# ADS1248_Eval_Board.net
KiCad netlist of a schematic drawn in EasyEDA
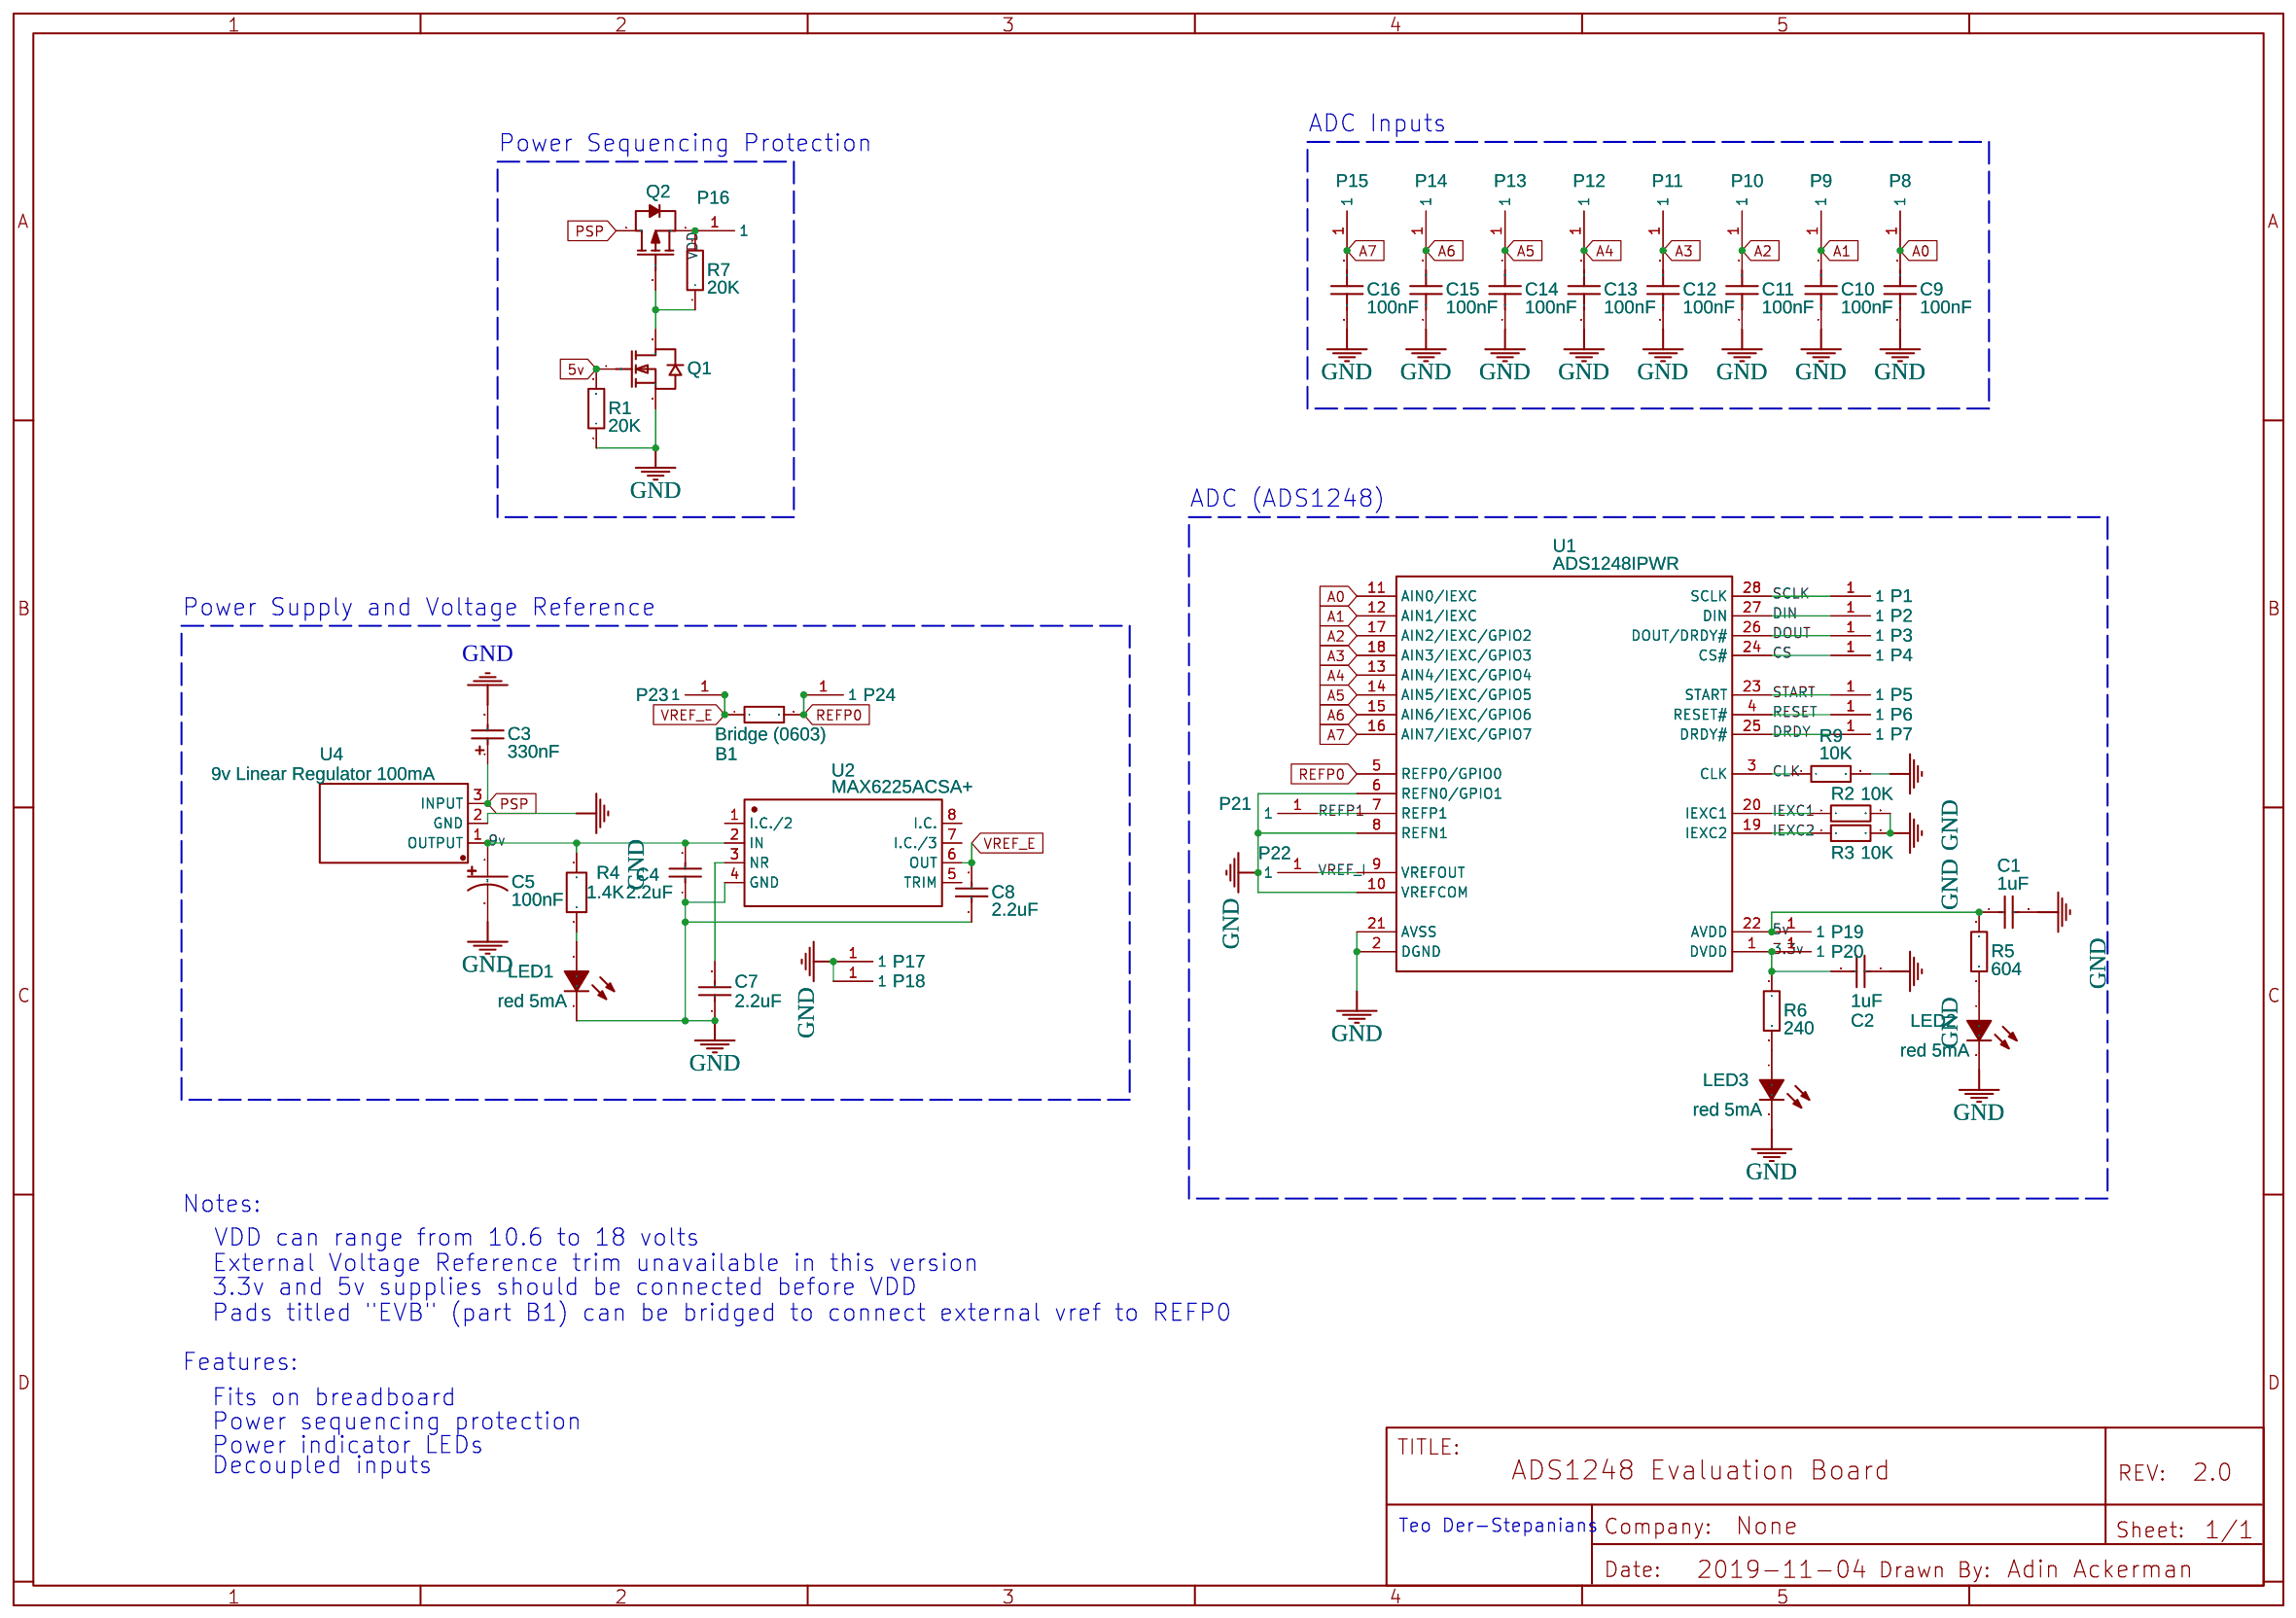
[diagram p0: schematic sheet]

(export (version "E")
  (design (tool "Eeschema 10.0.6"))
  (components
    (comp (ref "B1") (value "Bridge (0603)") (libsource (lib "") (part "Unknown_380_355")))
    (comp (ref "C1")
      (value "1uF")
      (fields
        (field (name "BOM_Manufacturer Part") "CL21B105KOFNNNE")
        (field (name "BOM_Supplier Part") "C24123")
      )
      (libsource (lib "") (part "CL21B105KOFNNNE"))
    )
    (comp (ref "C2")
      (value "1uF")
      (fields
        (field (name "BOM_Manufacturer Part") "CL21B105KOFNNNE")
        (field (name "BOM_Supplier Part") "C24123")
      )
      (libsource (lib "") (part "CL21B105KOFNNNE"))
    )
    (comp (ref "C3")
      (value "330nF")
      (fields
        (field (name "BOM_Manufacturer Part") "F921V334MAA")
        (field (name "BOM_Supplier Part") "C382101")
      )
      (libsource (lib "") (part "F921V334MAA"))
    )
    (comp (ref "C4")
      (value "2.2uF")
      (fields
        (field (name "BOM_Manufacturer Part") "CL21A225KAFNNNE")
        (field (name "BOM_Supplier Part") "C87994")
      )
      (libsource (lib "") (part "CL21A225KAFNNNE"))
    )
    (comp (ref "C5")
      (value "100nF")
      (fields
        (field (name "BOM_Manufacturer Part") "TMCP1D104MTRF")
        (field (name "BOM_Supplier Part") "C154088")
      )
      (libsource (lib "") (part "TMCP1D104MTRF"))
    )
    (comp (ref "C7")
      (value "2.2uF")
      (fields
        (field (name "BOM_Manufacturer Part") "CL21A225KAFNNNE")
        (field (name "BOM_Supplier Part") "C87994")
      )
      (libsource (lib "") (part "CL21A225KAFNNNE"))
    )
    (comp (ref "C8")
      (value "2.2uF")
      (fields
        (field (name "BOM_Manufacturer Part") "CL21A225KAFNNNE")
        (field (name "BOM_Supplier Part") "C87994")
      )
      (libsource (lib "") (part "CL21A225KAFNNNE"))
    )
    (comp (ref "C9")
      (value "100nF")
      (fields
        (field (name "BOM_Manufacturer Part") "CL10B104KB8NNNC")
        (field (name "BOM_Supplier Part") "C1591")
      )
      (libsource (lib "") (part "CL10B104KB8NNNC"))
    )
    (comp (ref "C10")
      (value "100nF")
      (fields
        (field (name "BOM_Manufacturer Part") "CL10B104KB8NNNC")
        (field (name "BOM_Supplier Part") "C1591")
      )
      (libsource (lib "") (part "CL10B104KB8NNNC"))
    )
    (comp (ref "C11")
      (value "100nF")
      (fields
        (field (name "BOM_Manufacturer Part") "CL10B104KB8NNNC")
        (field (name "BOM_Supplier Part") "C1591")
      )
      (libsource (lib "") (part "CL10B104KB8NNNC"))
    )
    (comp (ref "C12")
      (value "100nF")
      (fields
        (field (name "BOM_Manufacturer Part") "CL10B104KB8NNNC")
        (field (name "BOM_Supplier Part") "C1591")
      )
      (libsource (lib "") (part "CL10B104KB8NNNC"))
    )
    (comp (ref "C13")
      (value "100nF")
      (fields
        (field (name "BOM_Manufacturer Part") "CL10B104KB8NNNC")
        (field (name "BOM_Supplier Part") "C1591")
      )
      (libsource (lib "") (part "CL10B104KB8NNNC"))
    )
    (comp (ref "C14")
      (value "100nF")
      (fields
        (field (name "BOM_Manufacturer Part") "CL10B104KB8NNNC")
        (field (name "BOM_Supplier Part") "C1591")
      )
      (libsource (lib "") (part "CL10B104KB8NNNC"))
    )
    (comp (ref "C15")
      (value "100nF")
      (fields
        (field (name "BOM_Manufacturer Part") "CL10B104KB8NNNC")
        (field (name "BOM_Supplier Part") "C1591")
      )
      (libsource (lib "") (part "CL10B104KB8NNNC"))
    )
    (comp (ref "C16")
      (value "100nF")
      (fields
        (field (name "BOM_Manufacturer Part") "CL10B104KB8NNNC")
        (field (name "BOM_Supplier Part") "C1591")
      )
      (libsource (lib "") (part "CL10B104KB8NNNC"))
    )
    (comp (ref "LED1")
      (value "red 5mA")
      (fields
        (field (name "BOM_Manufacturer Part") "19-217/R6C-AL1M2VY/3T(GDB)")
        (field (name "BOM_Supplier Part") "C131266")
      )
      (libsource (lib "") (part "Unknown_295_490"))
    )
    (comp (ref "LED2")
      (value "red 5mA")
      (fields
        (field (name "BOM_Manufacturer Part") "19-217/R6C-AL1M2VY/3T(GDB)")
        (field (name "BOM_Supplier Part") "C131266")
      )
      (libsource (lib "") (part "Unknown_1005_515"))
    )
    (comp (ref "LED3")
      (value "red 5mA")
      (fields
        (field (name "BOM_Manufacturer Part") "19-217/R6C-AL1M2VY/3T(GDB)")
        (field (name "BOM_Supplier Part") "C131266")
      )
      (libsource (lib "") (part "Unknown_900_545"))
    )
    (comp (ref "P1") (value "Standard 100 mil pad") (libsource (lib "") (part "Unknown_920_295")))
    (comp (ref "P2") (value "Standard 100 mil pad") (libsource (lib "") (part "Unknown_920_305")))
    (comp (ref "P3") (value "Standard 100 mil pad") (libsource (lib "") (part "Unknown_920_315")))
    (comp (ref "P4") (value "Standard 100 mil pad") (libsource (lib "") (part "Unknown_920_325")))
    (comp (ref "P5") (value "Standard 100 mil pad") (libsource (lib "") (part "Unknown_920_345")))
    (comp (ref "P6") (value "Standard 100 mil pad") (libsource (lib "") (part "Unknown_920_355")))
    (comp (ref "P7") (value "Standard 100 mil pad") (libsource (lib "") (part "Unknown_920_365")))
    (comp (ref "P8") (value "Standard 100 mil pad") (libsource (lib "") (part "Unknown_955_120")))
    (comp (ref "P9") (value "Standard 100 mil pad") (libsource (lib "") (part "Unknown_915_120")))
    (comp (ref "P10") (value "Standard 100 mil pad") (libsource (lib "") (part "Unknown_875_120")))
    (comp (ref "P11") (value "Standard 100 mil pad") (libsource (lib "") (part "Unknown_835_120")))
    (comp (ref "P12") (value "Standard 100 mil pad") (libsource (lib "") (part "Unknown_795_120")))
    (comp (ref "P13") (value "Standard 100 mil pad") (libsource (lib "") (part "Unknown_755_120")))
    (comp (ref "P14") (value "Standard 100 mil pad") (libsource (lib "") (part "Unknown_715_120")))
    (comp (ref "P15") (value "Standard 100 mil pad") (libsource (lib "") (part "Unknown_675_120")))
    (comp (ref "P16") (value "Standard 100 mil pad") (libsource (lib "") (part "Unknown_345_110")))
    (comp (ref "P17") (value "Standard 100 mil pad") (libsource (lib "") (part "Unknown_415_480")))
    (comp (ref "P18") (value "Standard 100 mil pad") (libsource (lib "") (part "Unknown_415_490")))
    (comp (ref "P19") (value "Standard 100 mil pad") (libsource (lib "") (part "Unknown_890_465")))
    (comp (ref "P20") (value "Standard 100 mil pad") (libsource (lib "") (part "Unknown_890_475")))
    (comp (ref "P21") (value "Standard 100 mil pad") (libsource (lib "") (part "Unknown_660_405")))
    (comp (ref "P22") (value "Standard 100 mil pad") (libsource (lib "") (part "Unknown_660_435")))
    (comp (ref "P23") (value "Standard 100 mil pad") (libsource (lib "") (part "Unknown_360_345")))
    (comp (ref "P24") (value "Standard 100 mil pad") (libsource (lib "") (part "Unknown_400_345")))
    (comp (ref "Q1")
      (value "AO3402_C14385")
      (fields (field (name "BOM_Manufacturer Part") "AO3402") (field (name "BOM_Supplier Part") "C14385"))
      (libsource (lib "") (part "Unknown_315_180"))
    )
    (comp (ref "Q2")
      (value "AO3407A")
      (fields (field (name "BOM_Supplier Part") "C15155"))
      (libsource (lib "") (part "Unknown_325_120"))
    )
    (comp (ref "R1")
      (value "20K")
      (fields
        (field (name "BOM_Manufacturer Part") "RC0603FR-0720KL")
        (field (name "BOM_Supplier Part") "C105575")
      )
      (libsource (lib "") (part "RC0603FR-0720KL"))
    )
    (comp (ref "R2")
      (value "10K")
      (fields
        (field (name "BOM_Manufacturer Part") "RC0603FR-0710KL")
        (field (name "BOM_Supplier Part") "C98220")
      )
      (libsource (lib "") (part "RC0603FR-0710KL"))
    )
    (comp (ref "R3")
      (value "10K")
      (fields
        (field (name "BOM_Manufacturer Part") "RC0603FR-0710KL")
        (field (name "BOM_Supplier Part") "C98220")
      )
      (libsource (lib "") (part "RC0603FR-0710KL"))
    )
    (comp (ref "R4")
      (value "1.4K")
      (fields
        (field (name "BOM_Manufacturer Part") "ERJ3EKF1401V")
        (field (name "BOM_Supplier Part") "C402982")
      )
      (libsource (lib "") (part "ERJ3EKF1401V"))
    )
    (comp (ref "R5")
      (value "604")
      (fields
        (field (name "BOM_Manufacturer Part") "AC0603FR-07604RL")
        (field (name "BOM_Supplier Part") "C227993")
      )
      (libsource (lib "") (part "AC0603FR-07604RL"))
    )
    (comp (ref "R6")
      (value "240")
      (fields
        (field (name "BOM_Manufacturer Part") "0805W8F2400T5E")
        (field (name "BOM_Supplier Part") "C17572")
      )
      (libsource (lib "") (part "0805W8F2400T5E"))
    )
    (comp (ref "R7")
      (value "20K")
      (fields
        (field (name "BOM_Manufacturer Part") "RC0603FR-0720KL")
        (field (name "BOM_Supplier Part") "C105575")
      )
      (libsource (lib "") (part "RC0603FR-0720KL"))
    )
    (comp (ref "R9")
      (value "10K")
      (fields
        (field (name "BOM_Manufacturer Part") "RC0603FR-0710KL")
        (field (name "BOM_Supplier Part") "C98220")
      )
      (libsource (lib "") (part "RC0603FR-0710KL"))
    )
    (comp (ref "U1")
      (value "ADS1248IPWR")
      (fields (field (name "BOM_Supplier Part") "C30576"))
      (libsource (lib "") (part "Unknown_790_385"))
    )
    (comp (ref "U2") (value "MAX6225ACSA+") (libsource (lib "") (part "Unknown_420_425")))
    (comp (ref "U4")
      (value "9v Linear Regulator 100mA")
      (fields
        (field (name "BOM_Manufacturer Part") "AZ78L09RTR-E1")
        (field (name "BOM_Supplier Part") "C108741")
      )
      (libsource (lib "") (part "Unknown_190_410"))
    )
  )
  (nets
    (net (code "1") (name "/3.3v") (class "Default")
      (node (ref "C2") (pin "1") (pinfunction "1_1") (pintype "input"))
      (node (ref "P20") (pin "1") (pinfunction "1_1") (pintype "unspecified"))
      (node (ref "R6") (pin "1") (pinfunction "1_1") (pintype "input"))
      (node (ref "U1") (pin "1") (pinfunction "DVDD_1") (pintype "unspecified"))
    )
    (net (code "2") (name "/9v") (class "Default")
      (node (ref "C4") (pin "2") (pinfunction "2_2") (pintype "input"))
      (node (ref "C5") (pin "1") (pinfunction "1_1") (pintype "unspecified"))
      (node (ref "R4") (pin "2") (pinfunction "2_2") (pintype "unspecified"))
      (node (ref "U2") (pin "2") (pinfunction "IN_2") (pintype "unspecified"))
      (node (ref "U4") (pin "1") (pinfunction "OUTPUT_1") (pintype "unspecified"))
    )
    (net (code "3") (name "/CLK") (class "Default")
      (node (ref "R9") (pin "1") (pinfunction "1_1") (pintype "input"))
      (node (ref "U1") (pin "3") (pinfunction "CLK_3") (pintype "unspecified"))
    )
    (net (code "4") (name "/CS") (class "Default")
      (node (ref "P4") (pin "1") (pinfunction "1_1") (pintype "unspecified"))
      (node (ref "U1") (pin "24") (pinfunction "CS#_24") (pintype "unspecified"))
    )
    (net (code "5") (name "/DIN") (class "Default")
      (node (ref "P2") (pin "1") (pinfunction "1_1") (pintype "unspecified"))
      (node (ref "U1") (pin "27") (pinfunction "DIN_27") (pintype "unspecified"))
    )
    (net (code "6") (name "/DOUT") (class "Default")
      (node (ref "P3") (pin "1") (pinfunction "1_1") (pintype "unspecified"))
      (node (ref "U1") (pin "26") (pinfunction "DOUT/DRDY#_26") (pintype "unspecified"))
    )
    (net (code "7") (name "/DRDY") (class "Default")
      (node (ref "P7") (pin "1") (pinfunction "1_1") (pintype "unspecified"))
      (node (ref "U1") (pin "25") (pinfunction "DRDY#_25") (pintype "unspecified"))
    )
    (net (code "8") (name "/IEXC1") (class "Default")
      (node (ref "R2") (pin "1") (pinfunction "1_1") (pintype "input"))
      (node (ref "U1") (pin "20") (pinfunction "IEXC1_20") (pintype "unspecified"))
    )
    (net (code "9") (name "/IEXC2") (class "Default")
      (node (ref "R3") (pin "1") (pinfunction "1_1") (pintype "input"))
      (node (ref "U1") (pin "19") (pinfunction "IEXC2_19") (pintype "unspecified"))
    )
    (net (code "10") (name "/REFP1") (class "Default")
      (node (ref "P21") (pin "1") (pinfunction "1_1") (pintype "unspecified"))
      (node (ref "U1") (pin "7") (pinfunction "REFP1_7") (pintype "unspecified"))
    )
    (net (code "11") (name "/RESET") (class "Default")
      (node (ref "P6") (pin "1") (pinfunction "1_1") (pintype "unspecified"))
      (node (ref "U1") (pin "4") (pinfunction "RESET#_4") (pintype "unspecified"))
    )
    (net (code "12") (name "/SCLK") (class "Default")
      (node (ref "P1") (pin "1") (pinfunction "1_1") (pintype "unspecified"))
      (node (ref "U1") (pin "28") (pinfunction "SCLK_28") (pintype "unspecified"))
    )
    (net (code "13") (name "/START") (class "Default")
      (node (ref "P5") (pin "1") (pinfunction "1_1") (pintype "unspecified"))
      (node (ref "U1") (pin "23") (pinfunction "START_23") (pintype "unspecified"))
    )
    (net (code "14") (name "/VDD") (class "Default")
      (node (ref "P16") (pin "1") (pinfunction "1_1") (pintype "unspecified"))
      (node (ref "Q2") (pin "2") (pinfunction "S_2") (pintype "unspecified"))
      (node (ref "R7") (pin "2") (pinfunction "2_2") (pintype "input"))
    )
    (net (code "15") (name "/VREF_I") (class "Default")
      (node (ref "P22") (pin "1") (pinfunction "1_1") (pintype "unspecified"))
      (node (ref "U1") (pin "9") (pinfunction "VREFOUT_9") (pintype "unspecified"))
    )
    (net (code "16") (name "5v") (class "Default")
      (node (ref "C1") (pin "1") (pinfunction "1_1") (pintype "input"))
      (node (ref "P19") (pin "1") (pinfunction "1_1") (pintype "unspecified"))
      (node (ref "Q1") (pin "1") (pinfunction "G_1") (pintype "unspecified"))
      (node (ref "R1") (pin "2") (pinfunction "2_2") (pintype "input"))
      (node (ref "R5") (pin "2") (pinfunction "2_2") (pintype "unspecified"))
      (node (ref "U1") (pin "22") (pinfunction "AVDD_22") (pintype "unspecified"))
    )
    (net (code "17") (name "A0") (class "Default")
      (node (ref "C9") (pin "2") (pinfunction "2_2") (pintype "unspecified"))
      (node (ref "P8") (pin "1") (pinfunction "1_1") (pintype "unspecified"))
      (node (ref "U1") (pin "11") (pinfunction "AIN0/IEXC_11") (pintype "unspecified"))
    )
    (net (code "18") (name "A1") (class "Default")
      (node (ref "C10") (pin "2") (pinfunction "2_2") (pintype "unspecified"))
      (node (ref "P9") (pin "1") (pinfunction "1_1") (pintype "unspecified"))
      (node (ref "U1") (pin "12") (pinfunction "AIN1/IEXC_12") (pintype "unspecified"))
    )
    (net (code "19") (name "A2") (class "Default")
      (node (ref "C11") (pin "2") (pinfunction "2_2") (pintype "unspecified"))
      (node (ref "P10") (pin "1") (pinfunction "1_1") (pintype "unspecified"))
      (node (ref "U1") (pin "17") (pinfunction "AIN2/IEXC/GPIO2_17") (pintype "unspecified"))
    )
    (net (code "20") (name "A3") (class "Default")
      (node (ref "C12") (pin "2") (pinfunction "2_2") (pintype "unspecified"))
      (node (ref "P11") (pin "1") (pinfunction "1_1") (pintype "unspecified"))
      (node (ref "U1") (pin "18") (pinfunction "AIN3/IEXC/GPIO3_18") (pintype "unspecified"))
    )
    (net (code "21") (name "A4") (class "Default")
      (node (ref "C13") (pin "2") (pinfunction "2_2") (pintype "unspecified"))
      (node (ref "P12") (pin "1") (pinfunction "1_1") (pintype "unspecified"))
      (node (ref "U1") (pin "13") (pinfunction "AIN4/IEXC/GPIO4_13") (pintype "unspecified"))
    )
    (net (code "22") (name "A5") (class "Default")
      (node (ref "C14") (pin "2") (pinfunction "2_2") (pintype "unspecified"))
      (node (ref "P13") (pin "1") (pinfunction "1_1") (pintype "unspecified"))
      (node (ref "U1") (pin "14") (pinfunction "AIN5/IEXC/GPIO5_14") (pintype "unspecified"))
    )
    (net (code "23") (name "A6") (class "Default")
      (node (ref "C15") (pin "2") (pinfunction "2_2") (pintype "unspecified"))
      (node (ref "P14") (pin "1") (pinfunction "1_1") (pintype "unspecified"))
      (node (ref "U1") (pin "15") (pinfunction "AIN6/IEXC/GPIO6_15") (pintype "unspecified"))
    )
    (net (code "24") (name "A7") (class "Default")
      (node (ref "C16") (pin "2") (pinfunction "2_2") (pintype "unspecified"))
      (node (ref "P15") (pin "1") (pinfunction "1_1") (pintype "unspecified"))
      (node (ref "U1") (pin "16") (pinfunction "AIN7/IEXC/GPIO7_16") (pintype "unspecified"))
    )
    (net (code "25") (name "GND") (class "Default")
      (node (ref "C1") (pin "2") (pinfunction "2_2") (pintype "input"))
      (node (ref "C10") (pin "1") (pinfunction "1_1") (pintype "unspecified"))
      (node (ref "C11") (pin "1") (pinfunction "1_1") (pintype "unspecified"))
      (node (ref "C12") (pin "1") (pinfunction "1_1") (pintype "unspecified"))
      (node (ref "C13") (pin "1") (pinfunction "1_1") (pintype "unspecified"))
      (node (ref "C14") (pin "1") (pinfunction "1_1") (pintype "unspecified"))
      (node (ref "C15") (pin "1") (pinfunction "1_1") (pintype "unspecified"))
      (node (ref "C16") (pin "1") (pinfunction "1_1") (pintype "unspecified"))
      (node (ref "C2") (pin "2") (pinfunction "2_2") (pintype "input"))
      (node (ref "C3") (pin "2") (pinfunction "2_2") (pintype "input"))
      (node (ref "C4") (pin "1") (pinfunction "1_1") (pintype "input"))
      (node (ref "C5") (pin "2") (pinfunction "2_2") (pintype "unspecified"))
      (node (ref "C7") (pin "1") (pinfunction "1_1") (pintype "input"))
      (node (ref "C8") (pin "1") (pinfunction "1_1") (pintype "input"))
      (node (ref "C9") (pin "1") (pinfunction "1_1") (pintype "unspecified"))
      (node (ref "LED1") (pin "2") (pinfunction "C_2") (pintype "input"))
      (node (ref "LED2") (pin "2") (pinfunction "C_2") (pintype "input"))
      (node (ref "LED3") (pin "2") (pinfunction "C_2") (pintype "input"))
      (node (ref "P17") (pin "1") (pinfunction "1_1") (pintype "unspecified"))
      (node (ref "P18") (pin "1") (pinfunction "1_1") (pintype "unspecified"))
      (node (ref "Q1") (pin "2") (pinfunction "S_2") (pintype "unspecified"))
      (node (ref "R1") (pin "1") (pinfunction "1_1") (pintype "input"))
      (node (ref "R2") (pin "2") (pinfunction "2_2") (pintype "input"))
      (node (ref "R3") (pin "2") (pinfunction "2_2") (pintype "input"))
      (node (ref "R9") (pin "2") (pinfunction "2_2") (pintype "input"))
      (node (ref "U1") (pin "10") (pinfunction "VREFCOM_10") (pintype "unspecified"))
      (node (ref "U1") (pin "2") (pinfunction "DGND_2") (pintype "unspecified"))
      (node (ref "U1") (pin "21") (pinfunction "AVSS_21") (pintype "unspecified"))
      (node (ref "U1") (pin "6") (pinfunction "REFN0/GPIO1_6") (pintype "unspecified"))
      (node (ref "U1") (pin "8") (pinfunction "REFN1_8") (pintype "unspecified"))
      (node (ref "U2") (pin "4") (pinfunction "GND_4") (pintype "unspecified"))
      (node (ref "U4") (pin "2") (pinfunction "GND_2") (pintype "unspecified"))
    )
    (net (code "26") (name "Net-(LED1-A)") (class "Default")
      (node (ref "LED1") (pin "1") (pinfunction "A_1") (pintype "input"))
      (node (ref "R4") (pin "1") (pinfunction "1_1") (pintype "unspecified"))
    )
    (net (code "27") (name "Net-(LED2-A)") (class "Default")
      (node (ref "LED2") (pin "1") (pinfunction "A_1") (pintype "input"))
      (node (ref "R5") (pin "1") (pinfunction "1_1") (pintype "unspecified"))
    )
    (net (code "28") (name "Net-(LED3-A)") (class "Default")
      (node (ref "LED3") (pin "1") (pinfunction "A_1") (pintype "input"))
      (node (ref "R6") (pin "2") (pinfunction "2_2") (pintype "input"))
    )
    (net (code "29") (name "Net-(Q1-D)") (class "Default")
      (node (ref "Q1") (pin "3") (pinfunction "D_3") (pintype "unspecified"))
      (node (ref "Q2") (pin "1") (pinfunction "G_1") (pintype "unspecified"))
      (node (ref "R7") (pin "1") (pinfunction "1_1") (pintype "input"))
    )
    (net (code "30") (name "Net-(U2-NR)") (class "Default")
      (node (ref "C7") (pin "2") (pinfunction "2_2") (pintype "input"))
      (node (ref "U2") (pin "3") (pinfunction "NR_3") (pintype "unspecified"))
    )
    (net (code "31") (name "PSP") (class "Default")
      (node (ref "C3") (pin "1") (pinfunction "1_1") (pintype "input"))
      (node (ref "Q2") (pin "3") (pinfunction "D_3") (pintype "unspecified"))
      (node (ref "U4") (pin "3") (pinfunction "INPUT_3") (pintype "unspecified"))
    )
    (net (code "32") (name "REFP0") (class "Default")
      (node (ref "B1") (pin "2") (pinfunction "2_2") (pintype "input"))
      (node (ref "P24") (pin "1") (pinfunction "1_1") (pintype "unspecified"))
      (node (ref "U1") (pin "5") (pinfunction "REFP0/GPIO0_5") (pintype "unspecified"))
    )
    (net (code "33") (name "VREF_E") (class "Default")
      (node (ref "B1") (pin "1") (pinfunction "1_1") (pintype "input"))
      (node (ref "C8") (pin "2") (pinfunction "2_2") (pintype "input"))
      (node (ref "P23") (pin "1") (pinfunction "1_1") (pintype "unspecified"))
      (node (ref "U2") (pin "6") (pinfunction "OUT_6") (pintype "unspecified"))
    )
    (net (code "34") (name "unconnected-(U2-I.C.-Pad8)") (class "Default")
      (node (ref "U2") (pin "8") (pinfunction "I.C._8") (pintype "unspecified"))
    )
    (net (code "35") (name "unconnected-(U2-I.C.{slash}2-Pad1)") (class "Default")
      (node (ref "U2") (pin "1") (pinfunction "I.C./2_1") (pintype "unspecified"))
    )
    (net (code "36") (name "unconnected-(U2-I.C.{slash}3-Pad7)") (class "Default")
      (node (ref "U2") (pin "7") (pinfunction "I.C./3_7") (pintype "unspecified"))
    )
    (net (code "37") (name "unconnected-(U2-TRIM-Pad5)") (class "Default")
      (node (ref "U2") (pin "5") (pinfunction "TRIM_5") (pintype "unspecified"))
    )
  )
)
